# outputs.net
KiCad netlist of a schematic drawn in Altium Designer
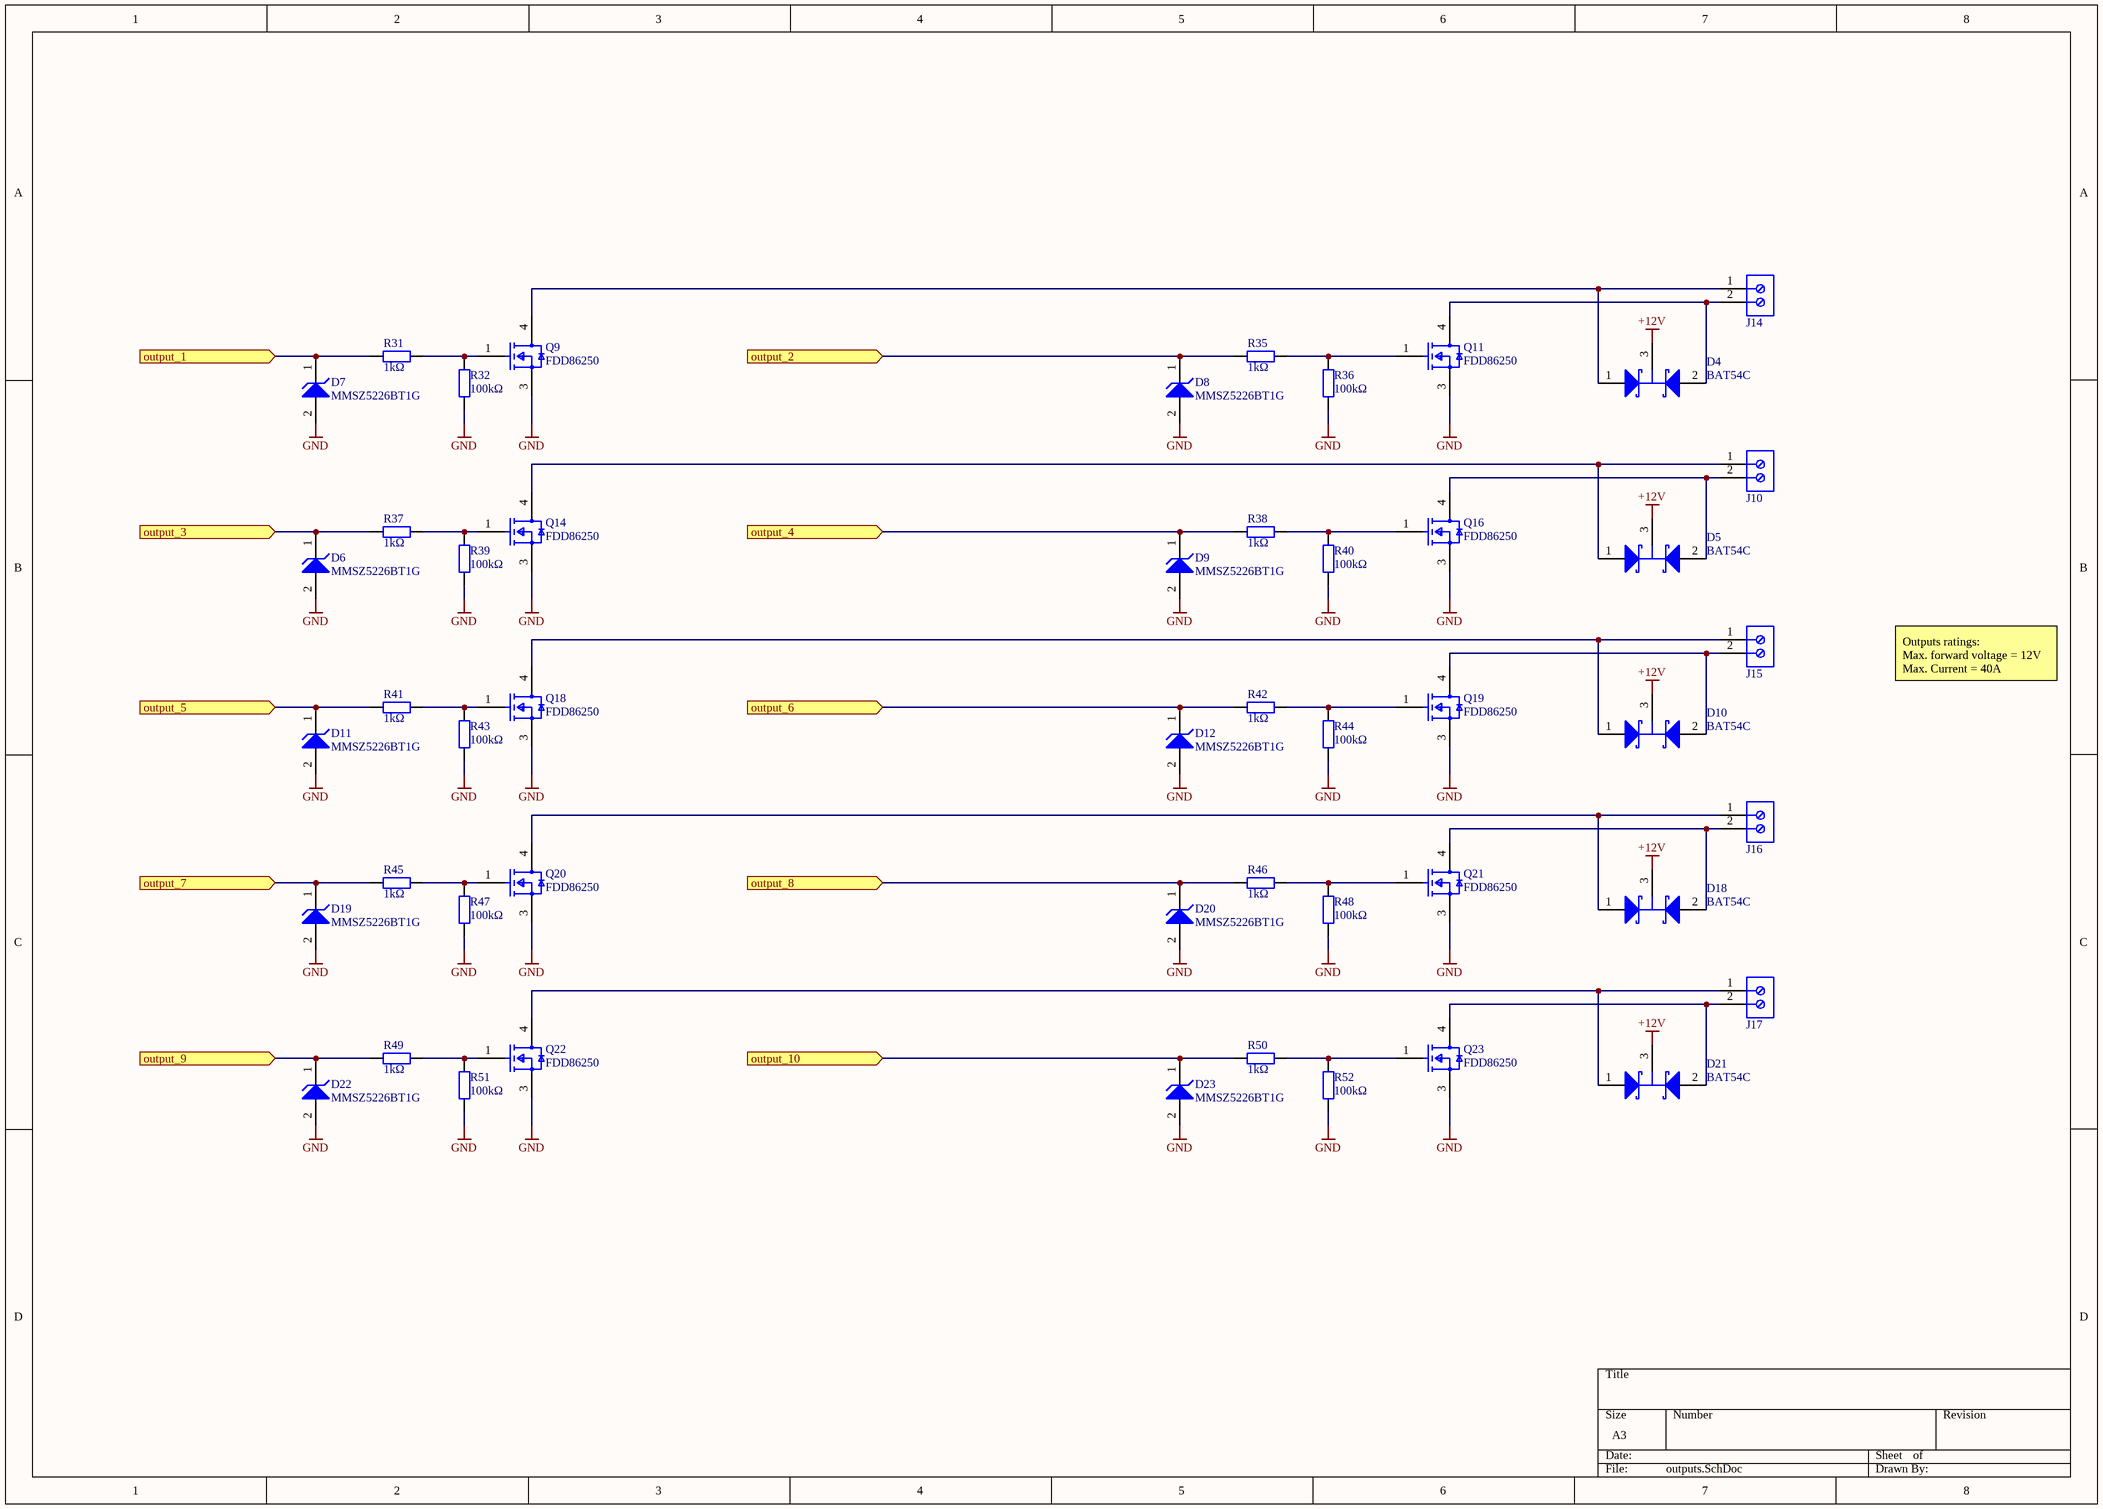
[diagram p0: outputs.SchDoc]

(export (version "E")
  (design (tool "Eeschema 10.0.6"))
  (components
    (comp (ref "D4")
      (value "BAT54C")
      (footprint "SOT-23")
      (description "Schottky Barrier Diode, 30 V, 3-Pin SOT23, RoHS, Tape and Reel")
      (fields (field (name "MANUFACTURER") "NXP Semiconductors"))
      (libsource (lib "integrated_library") (part "DIODE_BAT54C"))
    )
    (comp (ref "D5")
      (value "BAT54C")
      (footprint "SOT-23")
      (description "Schottky Barrier Diode, 30 V, 3-Pin SOT23, RoHS, Tape and Reel")
      (fields (field (name "MANUFACTURER") "NXP Semiconductors"))
      (libsource (lib "integrated_library") (part "DIODE_BAT54C"))
    )
    (comp (ref "D6")
      (value "MMSZ5226BT1G")
      (footprint "ONSC-SOD-123-2-425-04_V")
      (description "Zener Voltage Regulator, 500 mW, 2-Pin SOD-123, Pb-Free, Tape and Reel")
      (fields (field (name "MANUFACTURER") "On Semiconductor"))
      (libsource (lib "Altium Content Vault") (part "ONSC-K1A2-2"))
    )
    (comp (ref "D7")
      (value "MMSZ5226BT1G")
      (footprint "ONSC-SOD-123-2-425-04_V")
      (description "Zener Voltage Regulator, 500 mW, 2-Pin SOD-123, Pb-Free, Tape and Reel")
      (fields (field (name "MANUFACTURER") "On Semiconductor"))
      (libsource (lib "Altium Content Vault") (part "ONSC-K1A2-2"))
    )
    (comp (ref "D8")
      (value "MMSZ5226BT1G")
      (footprint "ONSC-SOD-123-2-425-04_V")
      (description "Zener Voltage Regulator, 500 mW, 2-Pin SOD-123, Pb-Free, Tape and Reel")
      (fields (field (name "MANUFACTURER") "On Semiconductor"))
      (libsource (lib "Altium Content Vault") (part "ONSC-K1A2-2"))
    )
    (comp (ref "D9")
      (value "MMSZ5226BT1G")
      (footprint "ONSC-SOD-123-2-425-04_V")
      (description "Zener Voltage Regulator, 500 mW, 2-Pin SOD-123, Pb-Free, Tape and Reel")
      (fields (field (name "MANUFACTURER") "On Semiconductor"))
      (libsource (lib "Altium Content Vault") (part "ONSC-K1A2-2"))
    )
    (comp (ref "D10")
      (value "BAT54C")
      (footprint "SOT-23")
      (description "Schottky Barrier Diode, 30 V, 3-Pin SOT23, RoHS, Tape and Reel")
      (fields (field (name "MANUFACTURER") "NXP Semiconductors"))
      (libsource (lib "integrated_library") (part "DIODE_BAT54C"))
    )
    (comp (ref "D11")
      (value "MMSZ5226BT1G")
      (footprint "ONSC-SOD-123-2-425-04_V")
      (description "Zener Voltage Regulator, 500 mW, 2-Pin SOD-123, Pb-Free, Tape and Reel")
      (fields (field (name "MANUFACTURER") "On Semiconductor"))
      (libsource (lib "Altium Content Vault") (part "ONSC-K1A2-2"))
    )
    (comp (ref "D12")
      (value "MMSZ5226BT1G")
      (footprint "ONSC-SOD-123-2-425-04_V")
      (description "Zener Voltage Regulator, 500 mW, 2-Pin SOD-123, Pb-Free, Tape and Reel")
      (fields (field (name "MANUFACTURER") "On Semiconductor"))
      (libsource (lib "Altium Content Vault") (part "ONSC-K1A2-2"))
    )
    (comp (ref "D18")
      (value "BAT54C")
      (footprint "SOT-23")
      (description "Schottky Barrier Diode, 30 V, 3-Pin SOT23, RoHS, Tape and Reel")
      (fields (field (name "MANUFACTURER") "NXP Semiconductors"))
      (libsource (lib "integrated_library") (part "DIODE_BAT54C"))
    )
    (comp (ref "D19")
      (value "MMSZ5226BT1G")
      (footprint "ONSC-SOD-123-2-425-04_V")
      (description "Zener Voltage Regulator, 500 mW, 2-Pin SOD-123, Pb-Free, Tape and Reel")
      (fields (field (name "MANUFACTURER") "On Semiconductor"))
      (libsource (lib "Altium Content Vault") (part "ONSC-K1A2-2"))
    )
    (comp (ref "D20")
      (value "MMSZ5226BT1G")
      (footprint "ONSC-SOD-123-2-425-04_V")
      (description "Zener Voltage Regulator, 500 mW, 2-Pin SOD-123, Pb-Free, Tape and Reel")
      (fields (field (name "MANUFACTURER") "On Semiconductor"))
      (libsource (lib "Altium Content Vault") (part "ONSC-K1A2-2"))
    )
    (comp (ref "D21")
      (value "BAT54C")
      (footprint "SOT-23")
      (description "Schottky Barrier Diode, 30 V, 3-Pin SOT23, RoHS, Tape and Reel")
      (fields (field (name "MANUFACTURER") "NXP Semiconductors"))
      (libsource (lib "integrated_library") (part "DIODE_BAT54C"))
    )
    (comp (ref "D22")
      (value "MMSZ5226BT1G")
      (footprint "ONSC-SOD-123-2-425-04_V")
      (description "Zener Voltage Regulator, 500 mW, 2-Pin SOD-123, Pb-Free, Tape and Reel")
      (fields (field (name "MANUFACTURER") "On Semiconductor"))
      (libsource (lib "Altium Content Vault") (part "ONSC-K1A2-2"))
    )
    (comp (ref "D23")
      (value "MMSZ5226BT1G")
      (footprint "ONSC-SOD-123-2-425-04_V")
      (description "Zener Voltage Regulator, 500 mW, 2-Pin SOD-123, Pb-Free, Tape and Reel")
      (fields (field (name "MANUFACTURER") "On Semiconductor"))
      (libsource (lib "Altium Content Vault") (part "ONSC-K1A2-2"))
    )
    (comp (ref "J10")
      (value "282836-2")
      (footprint "TECO-282836-2_V")
      (description "Female Header, Pitch 5 mm, 1 x 2 Position, Height 10 mm, Tail Length 3.5 mm, Rohs, Bulk")
      (fields (field (name "VOLTAGE") "300V") (field (name "MANUFACTURER") "TE Connectivity"))
      (libsource (lib "Altium Content Vault") (part "CN-1P-F-TB2"))
    )
    (comp (ref "J14")
      (value "282836-2")
      (footprint "TECO-282836-2_V")
      (description "Female Header, Pitch 5 mm, 1 x 2 Position, Height 10 mm, Tail Length 3.5 mm, Rohs, Bulk")
      (fields (field (name "VOLTAGE") "300V") (field (name "MANUFACTURER") "TE Connectivity"))
      (libsource (lib "Altium Content Vault") (part "CN-1P-F-TB2"))
    )
    (comp (ref "J15")
      (value "282836-2")
      (footprint "TECO-282836-2_V")
      (description "Female Header, Pitch 5 mm, 1 x 2 Position, Height 10 mm, Tail Length 3.5 mm, Rohs, Bulk")
      (fields (field (name "VOLTAGE") "300V") (field (name "MANUFACTURER") "TE Connectivity"))
      (libsource (lib "Altium Content Vault") (part "CN-1P-F-TB2"))
    )
    (comp (ref "J16")
      (value "282836-2")
      (footprint "TECO-282836-2_V")
      (description "Female Header, Pitch 5 mm, 1 x 2 Position, Height 10 mm, Tail Length 3.5 mm, Rohs, Bulk")
      (fields (field (name "VOLTAGE") "300V") (field (name "MANUFACTURER") "TE Connectivity"))
      (libsource (lib "Altium Content Vault") (part "CN-1P-F-TB2"))
    )
    (comp (ref "J17")
      (value "282836-2")
      (footprint "TECO-282836-2_V")
      (description "Female Header, Pitch 5 mm, 1 x 2 Position, Height 10 mm, Tail Length 3.5 mm, Rohs, Bulk")
      (fields (field (name "VOLTAGE") "300V") (field (name "MANUFACTURER") "TE Connectivity"))
      (libsource (lib "Altium Content Vault") (part "CN-1P-F-TB2"))
    )
    (comp (ref "Q9")
      (value "FDD86250")
      (footprint "FP-369AS-MFG")
      (description "MOSFET N-CH 150V 8A DPAK")
      (fields
        (field (name "MANUFACTURER") "ON Semiconductor")
        (field (name "OCTOPART") "https://octopart.com/fdd86250-on+semiconductor-84325855")
      )
      (libsource (lib "Altium Content Vault") (part "7ccf16d7e298eaa7d64fcf34af6bb8b"))
    )
    (comp (ref "Q11")
      (value "FDD86250")
      (footprint "FP-369AS-MFG")
      (description "MOSFET N-CH 150V 8A DPAK")
      (fields
        (field (name "MANUFACTURER") "ON Semiconductor")
        (field (name "OCTOPART") "https://octopart.com/fdd86250-on+semiconductor-84325855")
      )
      (libsource (lib "Altium Content Vault") (part "7ccf16d7e298eaa7d64fcf34af6bb8b"))
    )
    (comp (ref "Q14")
      (value "FDD86250")
      (footprint "FP-369AS-MFG")
      (description "MOSFET N-CH 150V 8A DPAK")
      (fields
        (field (name "MANUFACTURER") "ON Semiconductor")
        (field (name "OCTOPART") "https://octopart.com/fdd86250-on+semiconductor-84325855")
      )
      (libsource (lib "Altium Content Vault") (part "7ccf16d7e298eaa7d64fcf34af6bb8b"))
    )
    (comp (ref "Q16")
      (value "FDD86250")
      (footprint "FP-369AS-MFG")
      (description "MOSFET N-CH 150V 8A DPAK")
      (fields
        (field (name "MANUFACTURER") "ON Semiconductor")
        (field (name "OCTOPART") "https://octopart.com/fdd86250-on+semiconductor-84325855")
      )
      (libsource (lib "Altium Content Vault") (part "7ccf16d7e298eaa7d64fcf34af6bb8b"))
    )
    (comp (ref "Q18")
      (value "FDD86250")
      (footprint "FP-369AS-MFG")
      (description "MOSFET N-CH 150V 8A DPAK")
      (fields
        (field (name "MANUFACTURER") "ON Semiconductor")
        (field (name "OCTOPART") "https://octopart.com/fdd86250-on+semiconductor-84325855")
      )
      (libsource (lib "Altium Content Vault") (part "7ccf16d7e298eaa7d64fcf34af6bb8b"))
    )
    (comp (ref "Q19")
      (value "FDD86250")
      (footprint "FP-369AS-MFG")
      (description "MOSFET N-CH 150V 8A DPAK")
      (fields
        (field (name "MANUFACTURER") "ON Semiconductor")
        (field (name "OCTOPART") "https://octopart.com/fdd86250-on+semiconductor-84325855")
      )
      (libsource (lib "Altium Content Vault") (part "7ccf16d7e298eaa7d64fcf34af6bb8b"))
    )
    (comp (ref "Q20")
      (value "FDD86250")
      (footprint "FP-369AS-MFG")
      (description "MOSFET N-CH 150V 8A DPAK")
      (fields
        (field (name "MANUFACTURER") "ON Semiconductor")
        (field (name "OCTOPART") "https://octopart.com/fdd86250-on+semiconductor-84325855")
      )
      (libsource (lib "Altium Content Vault") (part "7ccf16d7e298eaa7d64fcf34af6bb8b"))
    )
    (comp (ref "Q21")
      (value "FDD86250")
      (footprint "FP-369AS-MFG")
      (description "MOSFET N-CH 150V 8A DPAK")
      (fields
        (field (name "MANUFACTURER") "ON Semiconductor")
        (field (name "OCTOPART") "https://octopart.com/fdd86250-on+semiconductor-84325855")
      )
      (libsource (lib "Altium Content Vault") (part "7ccf16d7e298eaa7d64fcf34af6bb8b"))
    )
    (comp (ref "Q22")
      (value "FDD86250")
      (footprint "FP-369AS-MFG")
      (description "MOSFET N-CH 150V 8A DPAK")
      (fields
        (field (name "MANUFACTURER") "ON Semiconductor")
        (field (name "OCTOPART") "https://octopart.com/fdd86250-on+semiconductor-84325855")
      )
      (libsource (lib "Altium Content Vault") (part "7ccf16d7e298eaa7d64fcf34af6bb8b"))
    )
    (comp (ref "Q23")
      (value "FDD86250")
      (footprint "FP-369AS-MFG")
      (description "MOSFET N-CH 150V 8A DPAK")
      (fields
        (field (name "MANUFACTURER") "ON Semiconductor")
        (field (name "OCTOPART") "https://octopart.com/fdd86250-on+semiconductor-84325855")
      )
      (libsource (lib "Altium Content Vault") (part "7ccf16d7e298eaa7d64fcf34af6bb8b"))
    )
    (comp (ref "R31")
      (value "1kΩ")
      (footprint "RESC2013X50X30ML20T20")
      (description "Resistor")
      (libsource (lib "") (part "Res_0805_1"))
    )
    (comp (ref "R32")
      (value "100kΩ")
      (footprint "RESC2013X50X30ML20T20")
      (description "Resistor")
      (libsource (lib "PCB_Project") (part "Res_0805"))
    )
    (comp (ref "R35")
      (value "1kΩ")
      (footprint "RESC2013X50X30ML20T20")
      (description "Resistor")
      (libsource (lib "") (part "Res_0805_1"))
    )
    (comp (ref "R36")
      (value "100kΩ")
      (footprint "RESC2013X50X30ML20T20")
      (description "Resistor")
      (libsource (lib "PCB_Project") (part "Res_0805"))
    )
    (comp (ref "R37")
      (value "1kΩ")
      (footprint "RESC2013X50X30ML20T20")
      (description "Resistor")
      (libsource (lib "") (part "Res_0805_1"))
    )
    (comp (ref "R38")
      (value "1kΩ")
      (footprint "RESC2013X50X30ML20T20")
      (description "Resistor")
      (libsource (lib "") (part "Res_0805_1"))
    )
    (comp (ref "R39")
      (value "100kΩ")
      (footprint "RESC2013X50X30ML20T20")
      (description "Resistor")
      (libsource (lib "PCB_Project") (part "Res_0805"))
    )
    (comp (ref "R40")
      (value "100kΩ")
      (footprint "RESC2013X50X30ML20T20")
      (description "Resistor")
      (libsource (lib "PCB_Project") (part "Res_0805"))
    )
    (comp (ref "R41")
      (value "1kΩ")
      (footprint "RESC2013X50X30ML20T20")
      (description "Resistor")
      (libsource (lib "") (part "Res_0805_1"))
    )
    (comp (ref "R42")
      (value "1kΩ")
      (footprint "RESC2013X50X30ML20T20")
      (description "Resistor")
      (libsource (lib "") (part "Res_0805_1"))
    )
    (comp (ref "R43")
      (value "100kΩ")
      (footprint "RESC2013X50X30ML20T20")
      (description "Resistor")
      (libsource (lib "PCB_Project") (part "Res_0805"))
    )
    (comp (ref "R44")
      (value "100kΩ")
      (footprint "RESC2013X50X30ML20T20")
      (description "Resistor")
      (libsource (lib "PCB_Project") (part "Res_0805"))
    )
    (comp (ref "R45")
      (value "1kΩ")
      (footprint "RESC2013X50X30ML20T20")
      (description "Resistor")
      (libsource (lib "") (part "Res_0805_1"))
    )
    (comp (ref "R46")
      (value "1kΩ")
      (footprint "RESC2013X50X30ML20T20")
      (description "Resistor")
      (libsource (lib "") (part "Res_0805_1"))
    )
    (comp (ref "R47")
      (value "100kΩ")
      (footprint "RESC2013X50X30ML20T20")
      (description "Resistor")
      (libsource (lib "PCB_Project") (part "Res_0805"))
    )
    (comp (ref "R48")
      (value "100kΩ")
      (footprint "RESC2013X50X30ML20T20")
      (description "Resistor")
      (libsource (lib "PCB_Project") (part "Res_0805"))
    )
    (comp (ref "R49")
      (value "1kΩ")
      (footprint "RESC2013X50X30ML20T20")
      (description "Resistor")
      (libsource (lib "") (part "Res_0805_1"))
    )
    (comp (ref "R50")
      (value "1kΩ")
      (footprint "RESC2013X50X30ML20T20")
      (description "Resistor")
      (libsource (lib "") (part "Res_0805_1"))
    )
    (comp (ref "R51")
      (value "100kΩ")
      (footprint "RESC2013X50X30ML20T20")
      (description "Resistor")
      (libsource (lib "PCB_Project") (part "Res_0805"))
    )
    (comp (ref "R52")
      (value "100kΩ")
      (footprint "RESC2013X50X30ML20T20")
      (description "Resistor")
      (libsource (lib "PCB_Project") (part "Res_0805"))
    )
  )
  (nets
    (net (code "1") (name "+12V") (class "Default")
      (node (ref "D10") (pin "3") (pinfunction "K_3") (pintype "passive"))
      (node (ref "D18") (pin "3") (pinfunction "K_3") (pintype "passive"))
      (node (ref "D21") (pin "3") (pinfunction "K_3") (pintype "passive"))
      (node (ref "D4") (pin "3") (pinfunction "K_3") (pintype "passive"))
      (node (ref "D5") (pin "3") (pinfunction "K_3") (pintype "passive"))
    )
    (net (code "2") (name "/output_1") (class "Default")
      (node (ref "D7") (pin "1") (pinfunction "K_1") (pintype "passive"))
      (node (ref "R31") (pin "1") (pinfunction "1_1") (pintype "passive"))
    )
    (net (code "3") (name "/output_2") (class "Default")
      (node (ref "D8") (pin "1") (pinfunction "K_1") (pintype "passive"))
      (node (ref "R35") (pin "1") (pinfunction "1_1") (pintype "passive"))
    )
    (net (code "4") (name "/output_3") (class "Default")
      (node (ref "D6") (pin "1") (pinfunction "K_1") (pintype "passive"))
      (node (ref "R37") (pin "1") (pinfunction "1_1") (pintype "passive"))
    )
    (net (code "5") (name "/output_4") (class "Default")
      (node (ref "D9") (pin "1") (pinfunction "K_1") (pintype "passive"))
      (node (ref "R38") (pin "1") (pinfunction "1_1") (pintype "passive"))
    )
    (net (code "6") (name "/output_5") (class "Default")
      (node (ref "D11") (pin "1") (pinfunction "K_1") (pintype "passive"))
      (node (ref "R41") (pin "1") (pinfunction "1_1") (pintype "passive"))
    )
    (net (code "7") (name "/output_6") (class "Default")
      (node (ref "D12") (pin "1") (pinfunction "K_1") (pintype "passive"))
      (node (ref "R42") (pin "1") (pinfunction "1_1") (pintype "passive"))
    )
    (net (code "8") (name "/output_7") (class "Default")
      (node (ref "D19") (pin "1") (pinfunction "K_1") (pintype "passive"))
      (node (ref "R45") (pin "1") (pinfunction "1_1") (pintype "passive"))
    )
    (net (code "9") (name "/output_8") (class "Default")
      (node (ref "D20") (pin "1") (pinfunction "K_1") (pintype "passive"))
      (node (ref "R46") (pin "1") (pinfunction "1_1") (pintype "passive"))
    )
    (net (code "10") (name "/output_9") (class "Default")
      (node (ref "D22") (pin "1") (pinfunction "K_1") (pintype "passive"))
      (node (ref "R49") (pin "1") (pinfunction "1_1") (pintype "passive"))
    )
    (net (code "11") (name "/output_10") (class "Default")
      (node (ref "D23") (pin "1") (pinfunction "K_1") (pintype "passive"))
      (node (ref "R50") (pin "1") (pinfunction "1_1") (pintype "passive"))
    )
    (net (code "12") (name "GND") (class "Default")
      (node (ref "D11") (pin "2") (pinfunction "A_2") (pintype "passive"))
      (node (ref "D12") (pin "2") (pinfunction "A_2") (pintype "passive"))
      (node (ref "D19") (pin "2") (pinfunction "A_2") (pintype "passive"))
      (node (ref "D20") (pin "2") (pinfunction "A_2") (pintype "passive"))
      (node (ref "D22") (pin "2") (pinfunction "A_2") (pintype "passive"))
      (node (ref "D23") (pin "2") (pinfunction "A_2") (pintype "passive"))
      (node (ref "D6") (pin "2") (pinfunction "A_2") (pintype "passive"))
      (node (ref "D7") (pin "2") (pinfunction "A_2") (pintype "passive"))
      (node (ref "D8") (pin "2") (pinfunction "A_2") (pintype "passive"))
      (node (ref "D9") (pin "2") (pinfunction "A_2") (pintype "passive"))
      (node (ref "Q11") (pin "3") (pinfunction "S_3") (pintype "passive"))
      (node (ref "Q14") (pin "3") (pinfunction "S_3") (pintype "passive"))
      (node (ref "Q16") (pin "3") (pinfunction "S_3") (pintype "passive"))
      (node (ref "Q18") (pin "3") (pinfunction "S_3") (pintype "passive"))
      (node (ref "Q19") (pin "3") (pinfunction "S_3") (pintype "passive"))
      (node (ref "Q20") (pin "3") (pinfunction "S_3") (pintype "passive"))
      (node (ref "Q21") (pin "3") (pinfunction "S_3") (pintype "passive"))
      (node (ref "Q22") (pin "3") (pinfunction "S_3") (pintype "passive"))
      (node (ref "Q23") (pin "3") (pinfunction "S_3") (pintype "passive"))
      (node (ref "Q9") (pin "3") (pinfunction "S_3") (pintype "passive"))
      (node (ref "R32") (pin "1") (pinfunction "1_1") (pintype "passive"))
      (node (ref "R36") (pin "1") (pinfunction "1_1") (pintype "passive"))
      (node (ref "R39") (pin "1") (pinfunction "1_1") (pintype "passive"))
      (node (ref "R40") (pin "1") (pinfunction "1_1") (pintype "passive"))
      (node (ref "R43") (pin "1") (pinfunction "1_1") (pintype "passive"))
      (node (ref "R44") (pin "1") (pinfunction "1_1") (pintype "passive"))
      (node (ref "R47") (pin "1") (pinfunction "1_1") (pintype "passive"))
      (node (ref "R48") (pin "1") (pinfunction "1_1") (pintype "passive"))
      (node (ref "R51") (pin "1") (pinfunction "1_1") (pintype "passive"))
      (node (ref "R52") (pin "1") (pinfunction "1_1") (pintype "passive"))
    )
    (net (code "13") (name "Net-(Q9-D)") (class "Default")
      (node (ref "D4") (pin "1") (pinfunction "A_1") (pintype "passive"))
      (node (ref "J14") (pin "1") (pinfunction "1_1") (pintype "passive"))
      (node (ref "Q9") (pin "4") (pinfunction "D_4") (pintype "passive"))
    )
    (net (code "14") (name "Net-(Q9-G)") (class "Default")
      (node (ref "Q9") (pin "1") (pinfunction "G_1") (pintype "passive"))
      (node (ref "R31") (pin "2") (pinfunction "2_2") (pintype "passive"))
      (node (ref "R32") (pin "2") (pinfunction "2_2") (pintype "passive"))
    )
    (net (code "15") (name "Net-(Q11-D)") (class "Default")
      (node (ref "D4") (pin "2") (pinfunction "A_2") (pintype "passive"))
      (node (ref "J14") (pin "2") (pinfunction "2_2") (pintype "passive"))
      (node (ref "Q11") (pin "4") (pinfunction "D_4") (pintype "passive"))
    )
    (net (code "16") (name "Net-(Q11-G)") (class "Default")
      (node (ref "Q11") (pin "1") (pinfunction "G_1") (pintype "passive"))
      (node (ref "R35") (pin "2") (pinfunction "2_2") (pintype "passive"))
      (node (ref "R36") (pin "2") (pinfunction "2_2") (pintype "passive"))
    )
    (net (code "17") (name "Net-(Q14-D)") (class "Default")
      (node (ref "D5") (pin "1") (pinfunction "A_1") (pintype "passive"))
      (node (ref "J10") (pin "1") (pinfunction "1_1") (pintype "passive"))
      (node (ref "Q14") (pin "4") (pinfunction "D_4") (pintype "passive"))
    )
    (net (code "18") (name "Net-(Q14-G)") (class "Default")
      (node (ref "Q14") (pin "1") (pinfunction "G_1") (pintype "passive"))
      (node (ref "R37") (pin "2") (pinfunction "2_2") (pintype "passive"))
      (node (ref "R39") (pin "2") (pinfunction "2_2") (pintype "passive"))
    )
    (net (code "19") (name "Net-(Q16-D)") (class "Default")
      (node (ref "D5") (pin "2") (pinfunction "A_2") (pintype "passive"))
      (node (ref "J10") (pin "2") (pinfunction "2_2") (pintype "passive"))
      (node (ref "Q16") (pin "4") (pinfunction "D_4") (pintype "passive"))
    )
    (net (code "20") (name "Net-(Q16-G)") (class "Default")
      (node (ref "Q16") (pin "1") (pinfunction "G_1") (pintype "passive"))
      (node (ref "R38") (pin "2") (pinfunction "2_2") (pintype "passive"))
      (node (ref "R40") (pin "2") (pinfunction "2_2") (pintype "passive"))
    )
    (net (code "21") (name "Net-(Q18-D)") (class "Default")
      (node (ref "D10") (pin "1") (pinfunction "A_1") (pintype "passive"))
      (node (ref "J15") (pin "1") (pinfunction "1_1") (pintype "passive"))
      (node (ref "Q18") (pin "4") (pinfunction "D_4") (pintype "passive"))
    )
    (net (code "22") (name "Net-(Q18-G)") (class "Default")
      (node (ref "Q18") (pin "1") (pinfunction "G_1") (pintype "passive"))
      (node (ref "R41") (pin "2") (pinfunction "2_2") (pintype "passive"))
      (node (ref "R43") (pin "2") (pinfunction "2_2") (pintype "passive"))
    )
    (net (code "23") (name "Net-(Q19-D)") (class "Default")
      (node (ref "D10") (pin "2") (pinfunction "A_2") (pintype "passive"))
      (node (ref "J15") (pin "2") (pinfunction "2_2") (pintype "passive"))
      (node (ref "Q19") (pin "4") (pinfunction "D_4") (pintype "passive"))
    )
    (net (code "24") (name "Net-(Q19-G)") (class "Default")
      (node (ref "Q19") (pin "1") (pinfunction "G_1") (pintype "passive"))
      (node (ref "R42") (pin "2") (pinfunction "2_2") (pintype "passive"))
      (node (ref "R44") (pin "2") (pinfunction "2_2") (pintype "passive"))
    )
    (net (code "25") (name "Net-(Q20-D)") (class "Default")
      (node (ref "D18") (pin "1") (pinfunction "A_1") (pintype "passive"))
      (node (ref "J16") (pin "1") (pinfunction "1_1") (pintype "passive"))
      (node (ref "Q20") (pin "4") (pinfunction "D_4") (pintype "passive"))
    )
    (net (code "26") (name "Net-(Q20-G)") (class "Default")
      (node (ref "Q20") (pin "1") (pinfunction "G_1") (pintype "passive"))
      (node (ref "R45") (pin "2") (pinfunction "2_2") (pintype "passive"))
      (node (ref "R47") (pin "2") (pinfunction "2_2") (pintype "passive"))
    )
    (net (code "27") (name "Net-(Q21-D)") (class "Default")
      (node (ref "D18") (pin "2") (pinfunction "A_2") (pintype "passive"))
      (node (ref "J16") (pin "2") (pinfunction "2_2") (pintype "passive"))
      (node (ref "Q21") (pin "4") (pinfunction "D_4") (pintype "passive"))
    )
    (net (code "28") (name "Net-(Q21-G)") (class "Default")
      (node (ref "Q21") (pin "1") (pinfunction "G_1") (pintype "passive"))
      (node (ref "R46") (pin "2") (pinfunction "2_2") (pintype "passive"))
      (node (ref "R48") (pin "2") (pinfunction "2_2") (pintype "passive"))
    )
    (net (code "29") (name "Net-(Q22-D)") (class "Default")
      (node (ref "D21") (pin "1") (pinfunction "A_1") (pintype "passive"))
      (node (ref "J17") (pin "1") (pinfunction "1_1") (pintype "passive"))
      (node (ref "Q22") (pin "4") (pinfunction "D_4") (pintype "passive"))
    )
    (net (code "30") (name "Net-(Q22-G)") (class "Default")
      (node (ref "Q22") (pin "1") (pinfunction "G_1") (pintype "passive"))
      (node (ref "R49") (pin "2") (pinfunction "2_2") (pintype "passive"))
      (node (ref "R51") (pin "2") (pinfunction "2_2") (pintype "passive"))
    )
    (net (code "31") (name "Net-(Q23-D)") (class "Default")
      (node (ref "D21") (pin "2") (pinfunction "A_2") (pintype "passive"))
      (node (ref "J17") (pin "2") (pinfunction "2_2") (pintype "passive"))
      (node (ref "Q23") (pin "4") (pinfunction "D_4") (pintype "passive"))
    )
    (net (code "32") (name "Net-(Q23-G)") (class "Default")
      (node (ref "Q23") (pin "1") (pinfunction "G_1") (pintype "passive"))
      (node (ref "R50") (pin "2") (pinfunction "2_2") (pintype "passive"))
      (node (ref "R52") (pin "2") (pinfunction "2_2") (pintype "passive"))
    )
  )
)
